# buttons.net
KiCad netlist of a schematic drawn in Altium Designer
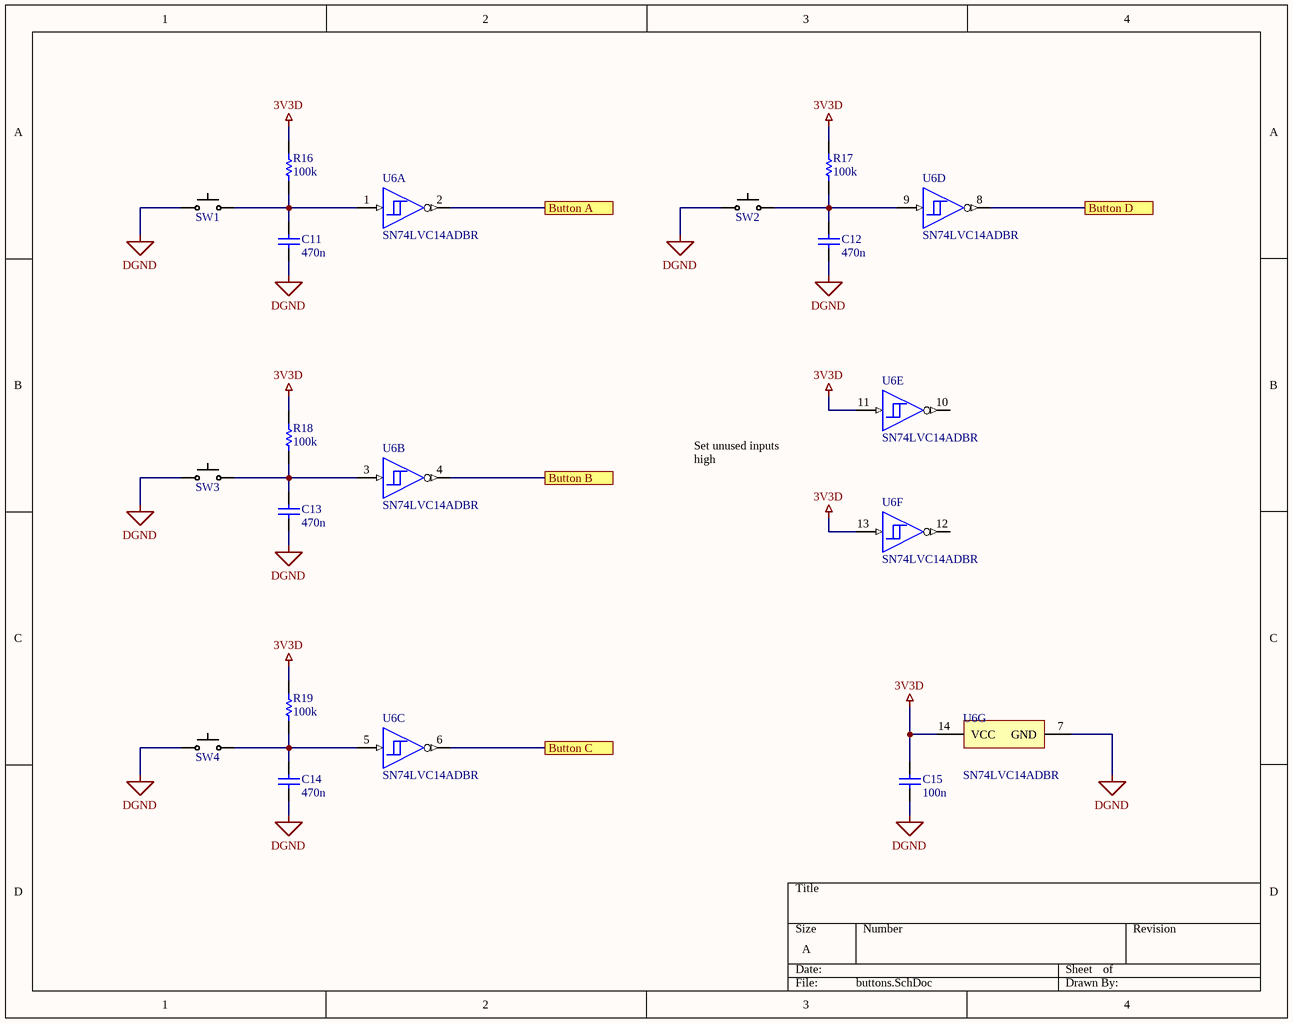
[diagram p0: buttons.SchDoc]

(export (version "E")
  (design (tool "Eeschema 10.0.6"))
  (components
    (comp (ref "C11")
      (value "470n")
      (footprint "C0805_med_density")
      (description "SMD Ceramic Capacitor")
      (fields (field (name "Comment") "CapCer"))
      (libsource (lib "passives") (part "CapCer"))
    )
    (comp (ref "C12")
      (value "470n")
      (footprint "C0805_med_density")
      (description "SMD Ceramic Capacitor")
      (fields (field (name "Comment") "CapCer"))
      (libsource (lib "passives") (part "CapCer"))
    )
    (comp (ref "C13")
      (value "470n")
      (footprint "C0805_med_density")
      (description "SMD Ceramic Capacitor")
      (fields (field (name "Comment") "CapCer"))
      (libsource (lib "passives") (part "CapCer"))
    )
    (comp (ref "C14")
      (value "470n")
      (footprint "C0805_med_density")
      (description "SMD Ceramic Capacitor")
      (fields (field (name "Comment") "CapCer"))
      (libsource (lib "passives") (part "CapCer"))
    )
    (comp (ref "C15")
      (value "100n")
      (footprint "C0805_med_density")
      (description "SMD Ceramic Capacitor")
      (fields (field (name "Comment") "CapCer"))
      (libsource (lib "passives") (part "CapCer"))
    )
    (comp (ref "R16")
      (value "100k")
      (footprint "R0805_med_density")
      (description "SMD Chip resistor")
      (fields (field (name "Comment") "ResChip"))
      (libsource (lib "passives") (part "ResChip"))
    )
    (comp (ref "R17")
      (value "100k")
      (footprint "R0805_med_density")
      (description "SMD Chip resistor")
      (fields (field (name "Comment") "ResChip"))
      (libsource (lib "passives") (part "ResChip"))
    )
    (comp (ref "R18")
      (value "100k")
      (footprint "R0805_med_density")
      (description "SMD Chip resistor")
      (fields (field (name "Comment") "ResChip"))
      (libsource (lib "passives") (part "ResChip"))
    )
    (comp (ref "R19")
      (value "100k")
      (footprint "R0805_med_density")
      (description "SMD Chip resistor")
      (fields (field (name "Comment") "ResChip"))
      (libsource (lib "passives") (part "ResChip"))
    )
    (comp (ref "SW1")
      (value "Switch")
      (footprint "PUSHBUTTON")
      (description "Push button switch, momentary, normally open")
      (libsource (lib "valves") (part "Switch"))
    )
    (comp (ref "SW2")
      (value "Switch")
      (footprint "PUSHBUTTON")
      (description "Push button switch, momentary, normally open")
      (libsource (lib "valves") (part "Switch"))
    )
    (comp (ref "SW3")
      (value "Switch")
      (footprint "PUSHBUTTON")
      (description "Push button switch, momentary, normally open")
      (libsource (lib "valves") (part "Switch"))
    )
    (comp (ref "SW4")
      (value "Switch")
      (footprint "PUSHBUTTON")
      (description "Push button switch, momentary, normally open")
      (libsource (lib "valves") (part "Switch"))
    )
    (comp (ref "U6")
      (value "SN74LVC14ADBR")
      (footprint "SOP-14")
      (description "Hex Schmitt-Trigger Inverter, DB0014A, LARGE T&R")
      (fields
        (field (name "GENERIC PART NUMBER") "SN74LVC14A")
        (field (name "MANUFACTURER") "Texas Instruments")
      )
      (libsource (lib "valves") (part "SN74LVC14"))
    )
  )
  (nets
    (net (code "1") (name "/Button A") (class "Default")
      (node (ref "U6") (pin "2") (pinfunction "~{1Y}_2") (pintype "output"))
    )
    (net (code "2") (name "/Button B") (class "Default")
      (node (ref "U6") (pin "4") (pinfunction "~{2Y}_4") (pintype "output"))
    )
    (net (code "3") (name "/Button C") (class "Default")
      (node (ref "U6") (pin "6") (pinfunction "~{3Y}_6") (pintype "output"))
    )
    (net (code "4") (name "/Button D") (class "Default")
      (node (ref "U6") (pin "8") (pinfunction "~{4Y}_8") (pintype "output"))
    )
    (net (code "5") (name "3V3D") (class "Default")
      (node (ref "C15") (pin "1") (pinfunction "1_1") (pintype "passive"))
      (node (ref "R16") (pin "2") (pinfunction "2_2") (pintype "passive"))
      (node (ref "R17") (pin "2") (pinfunction "2_2") (pintype "passive"))
      (node (ref "R18") (pin "2") (pinfunction "2_2") (pintype "passive"))
      (node (ref "R19") (pin "2") (pinfunction "2_2") (pintype "passive"))
      (node (ref "U6") (pin "11") (pinfunction "5A_11") (pintype "input"))
      (node (ref "U6") (pin "13") (pinfunction "6A_13") (pintype "input"))
      (node (ref "U6") (pin "14") (pinfunction "VCC_14") (pintype "power_in"))
    )
    (net (code "6") (name "DGND") (class "Default")
      (node (ref "C11") (pin "2") (pinfunction "2_2") (pintype "passive"))
      (node (ref "C12") (pin "2") (pinfunction "2_2") (pintype "passive"))
      (node (ref "C13") (pin "2") (pinfunction "2_2") (pintype "passive"))
      (node (ref "C14") (pin "2") (pinfunction "2_2") (pintype "passive"))
      (node (ref "C15") (pin "2") (pinfunction "2_2") (pintype "passive"))
      (node (ref "SW1") (pin "2") (pinfunction "2_2") (pintype "passive"))
      (node (ref "SW2") (pin "2") (pinfunction "2_2") (pintype "passive"))
      (node (ref "SW3") (pin "2") (pinfunction "2_2") (pintype "passive"))
      (node (ref "SW4") (pin "2") (pinfunction "2_2") (pintype "passive"))
      (node (ref "U6") (pin "7") (pinfunction "GND_7") (pintype "power_in"))
    )
    (net (code "7") (name "Net-(U6A-1A)") (class "Default")
      (node (ref "C11") (pin "1") (pinfunction "1_1") (pintype "passive"))
      (node (ref "R16") (pin "1") (pinfunction "1_1") (pintype "passive"))
      (node (ref "SW1") (pin "1") (pinfunction "1_1") (pintype "passive"))
      (node (ref "U6") (pin "1") (pinfunction "1A_1") (pintype "input"))
    )
    (net (code "8") (name "Net-(U6B-2A)") (class "Default")
      (node (ref "C13") (pin "1") (pinfunction "1_1") (pintype "passive"))
      (node (ref "R18") (pin "1") (pinfunction "1_1") (pintype "passive"))
      (node (ref "SW3") (pin "1") (pinfunction "1_1") (pintype "passive"))
      (node (ref "U6") (pin "3") (pinfunction "2A_3") (pintype "input"))
    )
    (net (code "9") (name "Net-(U6C-3A)") (class "Default")
      (node (ref "C14") (pin "1") (pinfunction "1_1") (pintype "passive"))
      (node (ref "R19") (pin "1") (pinfunction "1_1") (pintype "passive"))
      (node (ref "SW4") (pin "1") (pinfunction "1_1") (pintype "passive"))
      (node (ref "U6") (pin "5") (pinfunction "3A_5") (pintype "input"))
    )
    (net (code "10") (name "Net-(U6D-4A)") (class "Default")
      (node (ref "C12") (pin "1") (pinfunction "1_1") (pintype "passive"))
      (node (ref "R17") (pin "1") (pinfunction "1_1") (pintype "passive"))
      (node (ref "SW2") (pin "1") (pinfunction "1_1") (pintype "passive"))
      (node (ref "U6") (pin "9") (pinfunction "4A_9") (pintype "input"))
    )
    (net (code "11") (name "unconnected-(U6E-~{5Y}-Pad10)") (class "Default")
      (node (ref "U6") (pin "10") (pinfunction "~{5Y}_10") (pintype "output"))
    )
    (net (code "12") (name "unconnected-(U6F-~{6Y}-Pad12)") (class "Default")
      (node (ref "U6") (pin "12") (pinfunction "~{6Y}_12") (pintype "output"))
    )
  )
)
